# CSC_Connections_Temp.net
KiCad netlist of a schematic drawn in Altium Designer
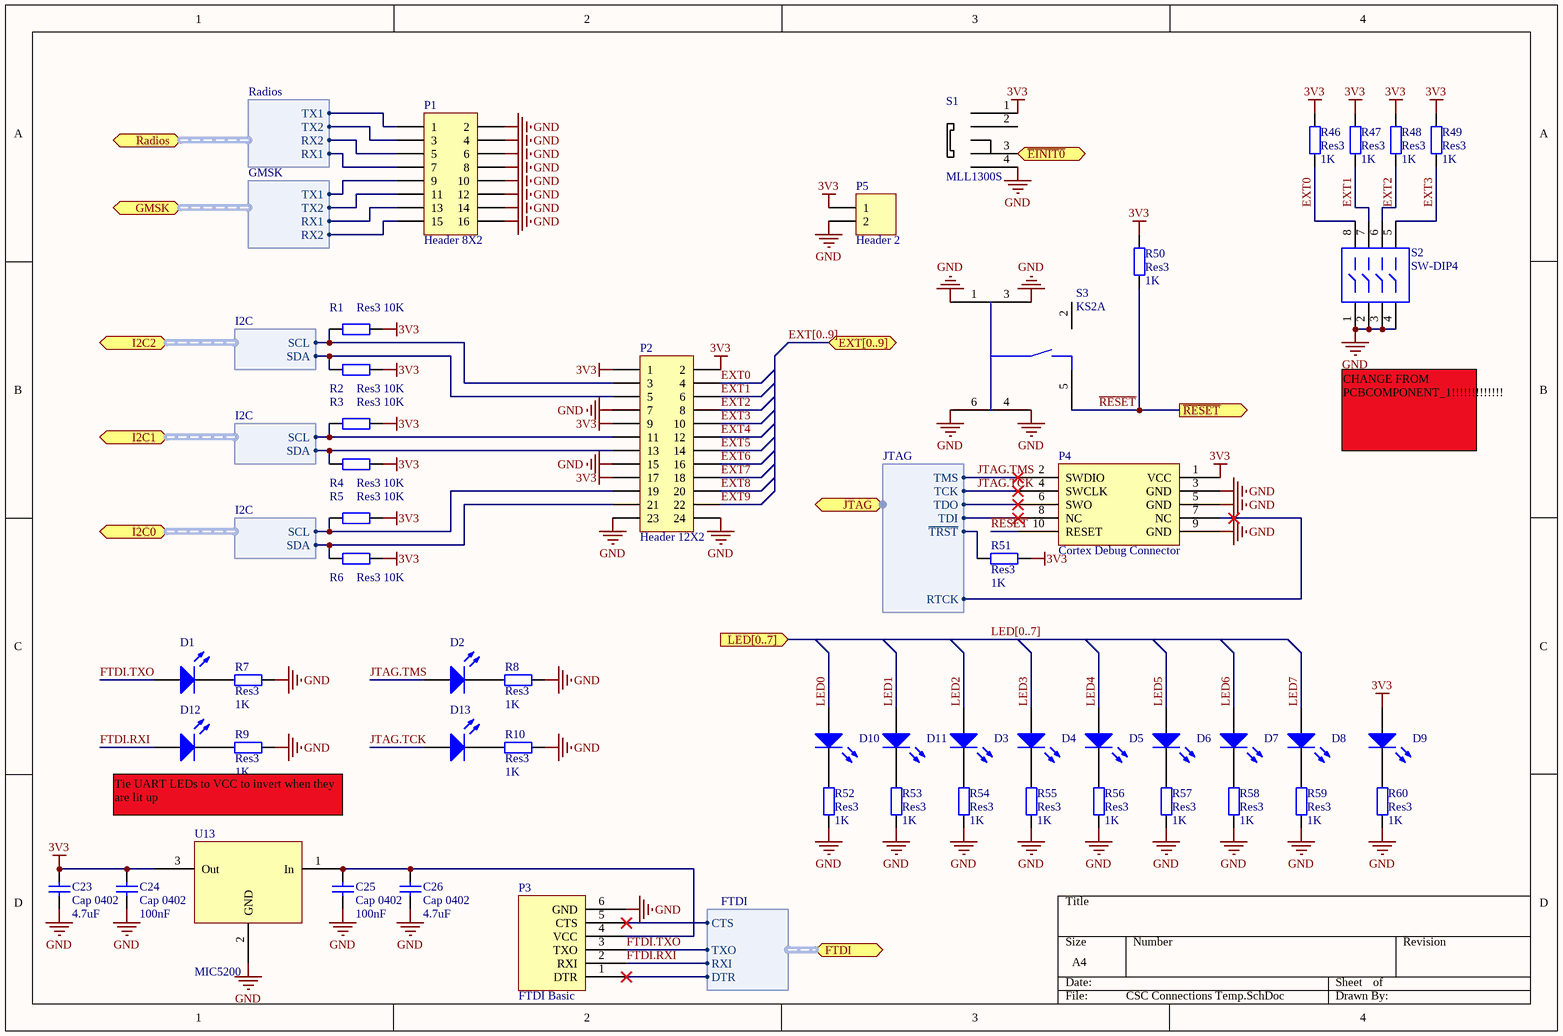
[diagram p0: CSC Connections Temp.SchDoc]

(export (version "E")
  (design (tool "Eeschema 10.0.6"))
  (components
    (comp (ref "C23")
      (value "Cap 0402")
      (footprint "CAPC1005X06L")
      (description "Capacitor")
      (fields (field (name "ALTIUM_VALUE") "4.7uF") (field (name "PUBLISHER") "Altium Limited"))
      (libsource (lib "CSC") (part "Cap 0402"))
    )
    (comp (ref "C24")
      (value "Cap 0402")
      (footprint "CAPC1005X06L")
      (description "Capacitor")
      (fields (field (name "ALTIUM_VALUE") "100nF") (field (name "PUBLISHER") "Altium Limited"))
      (libsource (lib "CSC") (part "Cap 0402"))
    )
    (comp (ref "C25")
      (value "Cap 0402")
      (footprint "CAPC1005X06L")
      (description "Capacitor")
      (fields (field (name "ALTIUM_VALUE") "100nF") (field (name "PUBLISHER") "Altium Limited"))
      (libsource (lib "CSC") (part "Cap 0402"))
    )
    (comp (ref "C26")
      (value "Cap 0402")
      (footprint "CAPC1005X06L")
      (description "Capacitor")
      (fields (field (name "ALTIUM_VALUE") "4.7uF") (field (name "PUBLISHER") "Altium Limited"))
      (libsource (lib "CSC") (part "Cap 0402"))
    )
    (comp (ref "D1")
      (value "LED - ASMT-Rx45")
      (footprint "ASMT-Rx45")
      (description "Typical INFRARED GaAs LED 0603")
      (fields (field (name "PUBLISHER") "Altium Limited"))
      (libsource (lib "CSC") (part "LED"))
    )
    (comp (ref "D2")
      (value "LED - ASMT-Rx45")
      (footprint "ASMT-Rx45")
      (description "Typical INFRARED GaAs LED 0603")
      (fields (field (name "PUBLISHER") "Altium Limited"))
      (libsource (lib "CSC") (part "LED"))
    )
    (comp (ref "D3")
      (value "LED - ASMT-Rx45")
      (footprint "ASMT-Rx45")
      (description "Typical INFRARED GaAs LED 0603")
      (fields (field (name "PUBLISHER") "Altium Limited"))
      (libsource (lib "CSC") (part "LED"))
    )
    (comp (ref "D4")
      (value "LED - ASMT-Rx45")
      (footprint "ASMT-Rx45")
      (description "Typical INFRARED GaAs LED 0603")
      (fields (field (name "PUBLISHER") "Altium Limited"))
      (libsource (lib "CSC") (part "LED"))
    )
    (comp (ref "D5")
      (value "LED - ASMT-Rx45")
      (footprint "ASMT-Rx45")
      (description "Typical INFRARED GaAs LED 0603")
      (fields (field (name "PUBLISHER") "Altium Limited"))
      (libsource (lib "CSC") (part "LED"))
    )
    (comp (ref "D6")
      (value "LED - ASMT-Rx45")
      (footprint "ASMT-Rx45")
      (description "Typical INFRARED GaAs LED 0603")
      (fields (field (name "PUBLISHER") "Altium Limited"))
      (libsource (lib "CSC") (part "LED"))
    )
    (comp (ref "D7")
      (value "LED - ASMT-Rx45")
      (footprint "ASMT-Rx45")
      (description "Typical INFRARED GaAs LED 0603")
      (fields (field (name "PUBLISHER") "Altium Limited"))
      (libsource (lib "CSC") (part "LED"))
    )
    (comp (ref "D8")
      (value "LED - ASMT-Rx45")
      (footprint "ASMT-Rx45")
      (description "Typical INFRARED GaAs LED 0603")
      (fields (field (name "PUBLISHER") "Altium Limited"))
      (libsource (lib "CSC") (part "LED"))
    )
    (comp (ref "D9")
      (value "LED - ASMT-Rx45")
      (footprint "ASMT-Rx45")
      (description "Typical INFRARED GaAs LED 0603")
      (fields (field (name "PUBLISHER") "Altium Limited"))
      (libsource (lib "CSC") (part "LED"))
    )
    (comp (ref "D10")
      (value "LED - ASMT-Rx45")
      (footprint "ASMT-Rx45")
      (description "Typical INFRARED GaAs LED 0603")
      (fields (field (name "PUBLISHER") "Altium Limited"))
      (libsource (lib "CSC") (part "LED"))
    )
    (comp (ref "D11")
      (value "LED - ASMT-Rx45")
      (footprint "ASMT-Rx45")
      (description "Typical INFRARED GaAs LED 0603")
      (fields (field (name "PUBLISHER") "Altium Limited"))
      (libsource (lib "CSC") (part "LED"))
    )
    (comp (ref "D12")
      (value "LED - ASMT-Rx45")
      (footprint "ASMT-Rx45")
      (description "Typical INFRARED GaAs LED 0603")
      (fields (field (name "PUBLISHER") "Altium Limited"))
      (libsource (lib "CSC") (part "LED"))
    )
    (comp (ref "D13")
      (value "LED - ASMT-Rx45")
      (footprint "ASMT-Rx45")
      (description "Typical INFRARED GaAs LED 0603")
      (fields (field (name "PUBLISHER") "Altium Limited"))
      (libsource (lib "CSC") (part "LED"))
    )
    (comp (ref "P1")
      (value "Header 8X2")
      (footprint "HDR2X8")
      (description "Header, 8-Pin, Dual row")
      (fields (field (name "PUBLISHER") "Altium Limited"))
      (libsource (lib "Miscellaneous Connectors") (part "Header 8X2"))
    )
    (comp (ref "P2")
      (value "Header 12X2")
      (footprint "HDR2X12")
      (description "Header, 12-Pin, Dual row")
      (fields (field (name "PUBLISHER") "Altium Limited"))
      (libsource (lib "Miscellaneous Connectors") (part "Header 12X2"))
    )
    (comp (ref "P3")
      (value "FTDI Basic")
      (footprint "FTDI BASIC")
      (libsource (lib "CSC") (part "FTDI Basic"))
    )
    (comp (ref "P4")
      (value "Cortex Debug Connector")
      (footprint "FTSH-105-01-L-DV-TR")
      (description "Mates with FFSD-05-D-12.00-01-N")
      (libsource (lib "CSC") (part "Cortex Debug Connector"))
    )
    (comp (ref "P5")
      (value "Header 2")
      (footprint "HDR1X2")
      (description "Header, 2-Pin")
      (fields (field (name "PUBLISHER") "Altium Limited"))
      (libsource (lib "Miscellaneous Connectors") (part "Header 2"))
    )
    (comp (ref "R1")
      (value "Res3")
      (footprint "RESC1005X06L")
      (description "Resistor")
      (fields (field (name "ALTIUM_VALUE") "10K") (field (name "PUBLISHER") "Altium Limited"))
      (libsource (lib "") (part "Res3_1"))
    )
    (comp (ref "R2")
      (value "Res3")
      (footprint "RESC1005X06L")
      (description "Resistor")
      (fields (field (name "ALTIUM_VALUE") "10K") (field (name "PUBLISHER") "Altium Limited"))
      (libsource (lib "") (part "Res3_1"))
    )
    (comp (ref "R3")
      (value "Res3")
      (footprint "RESC1005X06L")
      (description "Resistor")
      (fields (field (name "ALTIUM_VALUE") "10K") (field (name "PUBLISHER") "Altium Limited"))
      (libsource (lib "") (part "Res3_1"))
    )
    (comp (ref "R4")
      (value "Res3")
      (footprint "RESC1005X06L")
      (description "Resistor")
      (fields (field (name "ALTIUM_VALUE") "10K") (field (name "PUBLISHER") "Altium Limited"))
      (libsource (lib "") (part "Res3_1"))
    )
    (comp (ref "R5")
      (value "Res3")
      (footprint "RESC1005X06L")
      (description "Resistor")
      (fields (field (name "ALTIUM_VALUE") "10K") (field (name "PUBLISHER") "Altium Limited"))
      (libsource (lib "") (part "Res3_1"))
    )
    (comp (ref "R6")
      (value "Res3")
      (footprint "RESC1005X06L")
      (description "Resistor")
      (fields (field (name "ALTIUM_VALUE") "10K") (field (name "PUBLISHER") "Altium Limited"))
      (libsource (lib "") (part "Res3_1"))
    )
    (comp (ref "R7")
      (value "Res3")
      (footprint "RESC1005X06L")
      (description "Resistor")
      (fields (field (name "ALTIUM_VALUE") "1K") (field (name "PUBLISHER") "Altium Limited"))
      (libsource (lib "") (part "Res3_1"))
    )
    (comp (ref "R8")
      (value "Res3")
      (footprint "RESC1005X06L")
      (description "Resistor")
      (fields (field (name "ALTIUM_VALUE") "1K") (field (name "PUBLISHER") "Altium Limited"))
      (libsource (lib "") (part "Res3_1"))
    )
    (comp (ref "R9")
      (value "Res3")
      (footprint "RESC1005X06L")
      (description "Resistor")
      (fields (field (name "ALTIUM_VALUE") "1K") (field (name "PUBLISHER") "Altium Limited"))
      (libsource (lib "") (part "Res3_1"))
    )
    (comp (ref "R10")
      (value "Res3")
      (footprint "RESC1005X06L")
      (description "Resistor")
      (fields (field (name "ALTIUM_VALUE") "1K") (field (name "PUBLISHER") "Altium Limited"))
      (libsource (lib "") (part "Res3_1"))
    )
    (comp (ref "R46")
      (value "Res3")
      (footprint "RESC1005X06L")
      (description "Resistor")
      (fields (field (name "ALTIUM_VALUE") "1K") (field (name "PUBLISHER") "Altium Limited"))
      (libsource (lib "CSC") (part "Res3"))
    )
    (comp (ref "R47")
      (value "Res3")
      (footprint "RESC1005X06L")
      (description "Resistor")
      (fields (field (name "ALTIUM_VALUE") "1K") (field (name "PUBLISHER") "Altium Limited"))
      (libsource (lib "CSC") (part "Res3"))
    )
    (comp (ref "R48")
      (value "Res3")
      (footprint "RESC1005X06L")
      (description "Resistor")
      (fields (field (name "ALTIUM_VALUE") "1K") (field (name "PUBLISHER") "Altium Limited"))
      (libsource (lib "CSC") (part "Res3"))
    )
    (comp (ref "R49")
      (value "Res3")
      (footprint "RESC1005X06L")
      (description "Resistor")
      (fields (field (name "ALTIUM_VALUE") "1K") (field (name "PUBLISHER") "Altium Limited"))
      (libsource (lib "CSC") (part "Res3"))
    )
    (comp (ref "R50")
      (value "Res3")
      (footprint "RESC1005X06L")
      (description "Resistor")
      (fields (field (name "ALTIUM_VALUE") "1K") (field (name "PUBLISHER") "Altium Limited"))
      (libsource (lib "CSC") (part "Res3"))
    )
    (comp (ref "R51")
      (value "Res3")
      (footprint "RESC1005X06L")
      (description "Resistor")
      (fields (field (name "ALTIUM_VALUE") "1K") (field (name "PUBLISHER") "Altium Limited"))
      (libsource (lib "") (part "Res3_1"))
    )
    (comp (ref "R52")
      (value "Res3")
      (footprint "RESC1005X06L")
      (description "Resistor")
      (fields (field (name "ALTIUM_VALUE") "1K") (field (name "PUBLISHER") "Altium Limited"))
      (libsource (lib "CSC") (part "Res3"))
    )
    (comp (ref "R53")
      (value "Res3")
      (footprint "RESC1005X06L")
      (description "Resistor")
      (fields (field (name "ALTIUM_VALUE") "1K") (field (name "PUBLISHER") "Altium Limited"))
      (libsource (lib "CSC") (part "Res3"))
    )
    (comp (ref "R54")
      (value "Res3")
      (footprint "RESC1005X06L")
      (description "Resistor")
      (fields (field (name "ALTIUM_VALUE") "1K") (field (name "PUBLISHER") "Altium Limited"))
      (libsource (lib "CSC") (part "Res3"))
    )
    (comp (ref "R55")
      (value "Res3")
      (footprint "RESC1005X06L")
      (description "Resistor")
      (fields (field (name "ALTIUM_VALUE") "1K") (field (name "PUBLISHER") "Altium Limited"))
      (libsource (lib "CSC") (part "Res3"))
    )
    (comp (ref "R56")
      (value "Res3")
      (footprint "RESC1005X06L")
      (description "Resistor")
      (fields (field (name "ALTIUM_VALUE") "1K") (field (name "PUBLISHER") "Altium Limited"))
      (libsource (lib "CSC") (part "Res3"))
    )
    (comp (ref "R57")
      (value "Res3")
      (footprint "RESC1005X06L")
      (description "Resistor")
      (fields (field (name "ALTIUM_VALUE") "1K") (field (name "PUBLISHER") "Altium Limited"))
      (libsource (lib "CSC") (part "Res3"))
    )
    (comp (ref "R58")
      (value "Res3")
      (footprint "RESC1005X06L")
      (description "Resistor")
      (fields (field (name "ALTIUM_VALUE") "1K") (field (name "PUBLISHER") "Altium Limited"))
      (libsource (lib "CSC") (part "Res3"))
    )
    (comp (ref "R59")
      (value "Res3")
      (footprint "RESC1005X06L")
      (description "Resistor")
      (fields (field (name "ALTIUM_VALUE") "1K") (field (name "PUBLISHER") "Altium Limited"))
      (libsource (lib "CSC") (part "Res3"))
    )
    (comp (ref "R60")
      (value "Res3")
      (footprint "RESC1005X06L")
      (description "Resistor")
      (fields (field (name "ALTIUM_VALUE") "1K") (field (name "PUBLISHER") "Altium Limited"))
      (libsource (lib "CSC") (part "Res3"))
    )
    (comp (ref "S1")
      (value "MLL1300S")
      (footprint "MILL1300S")
      (description "Slide switch SP3T switch")
      (libsource (lib "CSC") (part "MLL1300S"))
    )
    (comp (ref "S2")
      (value "SW-DIP4")
      (footprint "PCBComponent_1")
      (description "DIP Switch - 1571983-5")
      (fields (field (name "PUBLISHER") "Altium Limited"))
      (libsource (lib "CSC") (part "SW-DIP4"))
    )
    (comp (ref "S3")
      (value "KS2A")
      (footprint "K5A2")
      (description "Tact Switch")
      (libsource (lib "CSC") (part "KS2A"))
    )
    (comp (ref "U13")
      (value "MIC5200")
      (footprint "SOT230P710X170-4L")
      (libsource (lib "CSC") (part "MIC5200"))
    )
  )
  (nets
    (net (code "6") (name "/CTS") (class "Default")
      (node (ref "P3") (pin "5") (pinfunction "CTS_5") (pintype "passive+no_connect"))
    )
    (net (code "7") (name "/DTR") (class "Default")
      (node (ref "P3") (pin "1") (pinfunction "DTR_1") (pintype "passive+no_connect"))
    )
    (net (code "8") (name "/EXT0") (class "Default")
      (node (ref "P2") (pin "4") (pinfunction "4_4") (pintype "passive"))
      (node (ref "R46") (pin "2") (pinfunction "2_2") (pintype "passive"))
      (node (ref "S2") (pin "8") (pinfunction "8_8") (pintype "passive"))
    )
    (net (code "9") (name "/EXT1") (class "Default")
      (node (ref "P2") (pin "6") (pinfunction "6_6") (pintype "passive"))
      (node (ref "R47") (pin "2") (pinfunction "2_2") (pintype "passive"))
      (node (ref "S2") (pin "7") (pinfunction "7_7") (pintype "passive"))
    )
    (net (code "10") (name "/EXT2") (class "Default")
      (node (ref "P2") (pin "8") (pinfunction "8_8") (pintype "passive"))
      (node (ref "R48") (pin "2") (pinfunction "2_2") (pintype "passive"))
      (node (ref "S2") (pin "6") (pinfunction "6_6") (pintype "passive"))
    )
    (net (code "11") (name "/EXT3") (class "Default")
      (node (ref "P2") (pin "10") (pinfunction "10_10") (pintype "passive"))
      (node (ref "R49") (pin "2") (pinfunction "2_2") (pintype "passive"))
      (node (ref "S2") (pin "5") (pinfunction "5_5") (pintype "passive"))
    )
    (net (code "12") (name "/EXT4") (class "Default")
      (node (ref "P2") (pin "12") (pinfunction "12_12") (pintype "passive"))
    )
    (net (code "13") (name "/EXT5") (class "Default")
      (node (ref "P2") (pin "14") (pinfunction "14_14") (pintype "passive"))
    )
    (net (code "14") (name "/EXT6") (class "Default")
      (node (ref "P2") (pin "16") (pinfunction "16_16") (pintype "passive"))
    )
    (net (code "15") (name "/EXT7") (class "Default")
      (node (ref "P2") (pin "18") (pinfunction "18_18") (pintype "passive"))
    )
    (net (code "16") (name "/EXT8") (class "Default")
      (node (ref "P2") (pin "20") (pinfunction "20_20") (pintype "passive"))
    )
    (net (code "17") (name "/EXT9") (class "Default")
      (node (ref "P2") (pin "22") (pinfunction "22_22") (pintype "passive"))
    )
    (net (code "19") (name "/FTDI.RXI") (class "Default")
      (node (ref "D12") (pin "1") (pinfunction "A_1") (pintype "passive"))
      (node (ref "P3") (pin "2") (pinfunction "RXI_2") (pintype "passive"))
    )
    (net (code "20") (name "/FTDI.TXO") (class "Default")
      (node (ref "D1") (pin "1") (pinfunction "A_1") (pintype "passive"))
      (node (ref "P3") (pin "3") (pinfunction "TXO_3") (pintype "passive"))
    )
    (net (code "21") (name "/JTAG.TCK") (class "Default")
      (node (ref "D13") (pin "1") (pinfunction "A_1") (pintype "passive"))
      (node (ref "P4") (pin "4") (pinfunction "SWCLK_4") (pintype "passive"))
    )
    (net (code "22") (name "/JTAG.TMS") (class "Default")
      (node (ref "D2") (pin "1") (pinfunction "A_1") (pintype "passive"))
      (node (ref "P4") (pin "2") (pinfunction "SWDIO_2") (pintype "passive"))
    )
    (net (code "23") (name "/LED0") (class "Default")
      (node (ref "D10") (pin "1") (pinfunction "A_1") (pintype "passive"))
    )
    (net (code "24") (name "/LED1") (class "Default")
      (node (ref "D11") (pin "1") (pinfunction "A_1") (pintype "passive"))
    )
    (net (code "25") (name "/LED2") (class "Default")
      (node (ref "D3") (pin "1") (pinfunction "A_1") (pintype "passive"))
    )
    (net (code "26") (name "/LED3") (class "Default")
      (node (ref "D4") (pin "1") (pinfunction "A_1") (pintype "passive"))
    )
    (net (code "27") (name "/LED4") (class "Default")
      (node (ref "D5") (pin "1") (pinfunction "A_1") (pintype "passive"))
    )
    (net (code "28") (name "/LED5") (class "Default")
      (node (ref "D6") (pin "1") (pinfunction "A_1") (pintype "passive"))
    )
    (net (code "29") (name "/LED6") (class "Default")
      (node (ref "D7") (pin "1") (pinfunction "A_1") (pintype "passive"))
    )
    (net (code "30") (name "/LED7") (class "Default")
      (node (ref "D8") (pin "1") (pinfunction "A_1") (pintype "passive"))
    )
    (net (code "32") (name "/RTCK") (class "Default")
      (node (ref "P4") (pin "7") (pinfunction "NC_7") (pintype "passive"))
    )
    (net (code "33") (name "/TDI") (class "Default")
      (node (ref "P4") (pin "8") (pinfunction "NC_8") (pintype "passive+no_connect"))
    )
    (net (code "34") (name "/TDO") (class "Default")
      (node (ref "P4") (pin "6") (pinfunction "SWO_6") (pintype "passive+no_connect"))
    )
    (net (code "40") (name "/~{EINIT0}") (class "Default")
      (node (ref "S1") (pin "3") (pinfunction "3_3") (pintype "passive"))
    )
    (net (code "41") (name "/~{RESET}") (class "Default")
      (node (ref "P4") (pin "10") (pinfunction "RESET_10") (pintype "passive"))
      (node (ref "R50") (pin "2") (pinfunction "2_2") (pintype "passive"))
      (node (ref "S3") (pin "5") (pinfunction "5_5") (pintype "passive"))
    )
    (net (code "42") (name "/~{TRST}") (class "Default")
      (node (ref "R51") (pin "1") (pinfunction "1_1") (pintype "passive"))
    )
    (net (code "43") (name "3V3") (class "Default")
      (node (ref "C23") (pin "2") (pinfunction "2_2") (pintype "passive"))
      (node (ref "C24") (pin "2") (pinfunction "2_2") (pintype "passive"))
      (node (ref "D9") (pin "1") (pinfunction "A_1") (pintype "passive"))
      (node (ref "P2") (pin "1") (pinfunction "1_1") (pintype "passive"))
      (node (ref "P2") (pin "17") (pinfunction "17_17") (pintype "passive"))
      (node (ref "P2") (pin "2") (pinfunction "2_2") (pintype "passive"))
      (node (ref "P2") (pin "9") (pinfunction "9_9") (pintype "passive"))
      (node (ref "P4") (pin "1") (pinfunction "VCC_1") (pintype "passive"))
      (node (ref "P5") (pin "1") (pinfunction "1_1") (pintype "passive"))
      (node (ref "R1") (pin "2") (pinfunction "2_2") (pintype "passive"))
      (node (ref "R2") (pin "2") (pinfunction "2_2") (pintype "passive"))
      (node (ref "R3") (pin "2") (pinfunction "2_2") (pintype "passive"))
      (node (ref "R4") (pin "2") (pinfunction "2_2") (pintype "passive"))
      (node (ref "R46") (pin "1") (pinfunction "1_1") (pintype "passive"))
      (node (ref "R47") (pin "1") (pinfunction "1_1") (pintype "passive"))
      (node (ref "R48") (pin "1") (pinfunction "1_1") (pintype "passive"))
      (node (ref "R49") (pin "1") (pinfunction "1_1") (pintype "passive"))
      (node (ref "R5") (pin "2") (pinfunction "2_2") (pintype "passive"))
      (node (ref "R50") (pin "1") (pinfunction "1_1") (pintype "passive"))
      (node (ref "R51") (pin "2") (pinfunction "2_2") (pintype "passive"))
      (node (ref "R6") (pin "2") (pinfunction "2_2") (pintype "passive"))
      (node (ref "S1") (pin "1") (pinfunction "1_1") (pintype "passive"))
      (node (ref "U13") (pin "3") (pinfunction "Out_3") (pintype "power_in"))
    )
    (net (code "44") (name "GND") (class "Default")
      (node (ref "C23") (pin "1") (pinfunction "1_1") (pintype "passive"))
      (node (ref "C24") (pin "1") (pinfunction "1_1") (pintype "passive"))
      (node (ref "C25") (pin "1") (pinfunction "1_1") (pintype "passive"))
      (node (ref "C26") (pin "1") (pinfunction "1_1") (pintype "passive"))
      (node (ref "P1") (pin "10") (pinfunction "10_10") (pintype "passive"))
      (node (ref "P1") (pin "12") (pinfunction "12_12") (pintype "passive"))
      (node (ref "P1") (pin "14") (pinfunction "14_14") (pintype "passive"))
      (node (ref "P1") (pin "16") (pinfunction "16_16") (pintype "passive"))
      (node (ref "P1") (pin "2") (pinfunction "2_2") (pintype "passive"))
      (node (ref "P1") (pin "4") (pinfunction "4_4") (pintype "passive"))
      (node (ref "P1") (pin "6") (pinfunction "6_6") (pintype "passive"))
      (node (ref "P1") (pin "8") (pinfunction "8_8") (pintype "passive"))
      (node (ref "P2") (pin "15") (pinfunction "15_15") (pintype "passive"))
      (node (ref "P2") (pin "23") (pinfunction "23_23") (pintype "passive"))
      (node (ref "P2") (pin "24") (pinfunction "24_24") (pintype "passive"))
      (node (ref "P2") (pin "7") (pinfunction "7_7") (pintype "passive"))
      (node (ref "P3") (pin "6") (pinfunction "GND_6") (pintype "passive"))
      (node (ref "P4") (pin "3") (pinfunction "GND_3") (pintype "passive"))
      (node (ref "P4") (pin "5") (pinfunction "GND_5") (pintype "passive"))
      (node (ref "P4") (pin "9") (pinfunction "GND_9") (pintype "passive"))
      (node (ref "P5") (pin "2") (pinfunction "2_2") (pintype "passive"))
      (node (ref "R10") (pin "2") (pinfunction "2_2") (pintype "passive"))
      (node (ref "R52") (pin "2") (pinfunction "2_2") (pintype "passive"))
      (node (ref "R53") (pin "2") (pinfunction "2_2") (pintype "passive"))
      (node (ref "R54") (pin "2") (pinfunction "2_2") (pintype "passive"))
      (node (ref "R55") (pin "2") (pinfunction "2_2") (pintype "passive"))
      (node (ref "R56") (pin "2") (pinfunction "2_2") (pintype "passive"))
      (node (ref "R57") (pin "2") (pinfunction "2_2") (pintype "passive"))
      (node (ref "R58") (pin "2") (pinfunction "2_2") (pintype "passive"))
      (node (ref "R59") (pin "2") (pinfunction "2_2") (pintype "passive"))
      (node (ref "R60") (pin "2") (pinfunction "2_2") (pintype "passive"))
      (node (ref "R7") (pin "2") (pinfunction "2_2") (pintype "passive"))
      (node (ref "R8") (pin "2") (pinfunction "2_2") (pintype "passive"))
      (node (ref "R9") (pin "2") (pinfunction "2_2") (pintype "passive"))
      (node (ref "S1") (pin "4") (pinfunction "4_4") (pintype "passive"))
      (node (ref "S2") (pin "1") (pinfunction "1_1") (pintype "passive"))
      (node (ref "S2") (pin "2") (pinfunction "2_2") (pintype "passive"))
      (node (ref "S2") (pin "3") (pinfunction "3_3") (pintype "passive"))
      (node (ref "S2") (pin "4") (pinfunction "4_4") (pintype "passive"))
      (node (ref "S3") (pin "1") (pinfunction "1_1") (pintype "power_in"))
      (node (ref "S3") (pin "3") (pinfunction "3_3") (pintype "power_in"))
      (node (ref "S3") (pin "4") (pinfunction "4_4") (pintype "power_in"))
      (node (ref "S3") (pin "6") (pinfunction "6_6") (pintype "power_in"))
      (node (ref "U13") (pin "2") (pinfunction "GND_2") (pintype "power_in"))
    )
    (net (code "45") (name "Net-(D1-K)") (class "Default")
      (node (ref "D1") (pin "2") (pinfunction "K_2") (pintype "passive"))
      (node (ref "R7") (pin "1") (pinfunction "1_1") (pintype "passive"))
    )
    (net (code "46") (name "Net-(D2-K)") (class "Default")
      (node (ref "D2") (pin "2") (pinfunction "K_2") (pintype "passive"))
      (node (ref "R8") (pin "1") (pinfunction "1_1") (pintype "passive"))
    )
    (net (code "47") (name "Net-(D3-K)") (class "Default")
      (node (ref "D3") (pin "2") (pinfunction "K_2") (pintype "passive"))
      (node (ref "R54") (pin "1") (pinfunction "1_1") (pintype "passive"))
    )
    (net (code "48") (name "Net-(D4-K)") (class "Default")
      (node (ref "D4") (pin "2") (pinfunction "K_2") (pintype "passive"))
      (node (ref "R55") (pin "1") (pinfunction "1_1") (pintype "passive"))
    )
    (net (code "49") (name "Net-(D5-K)") (class "Default")
      (node (ref "D5") (pin "2") (pinfunction "K_2") (pintype "passive"))
      (node (ref "R56") (pin "1") (pinfunction "1_1") (pintype "passive"))
    )
    (net (code "50") (name "Net-(D6-K)") (class "Default")
      (node (ref "D6") (pin "2") (pinfunction "K_2") (pintype "passive"))
      (node (ref "R57") (pin "1") (pinfunction "1_1") (pintype "passive"))
    )
    (net (code "51") (name "Net-(D7-K)") (class "Default")
      (node (ref "D7") (pin "2") (pinfunction "K_2") (pintype "passive"))
      (node (ref "R58") (pin "1") (pinfunction "1_1") (pintype "passive"))
    )
    (net (code "52") (name "Net-(D8-K)") (class "Default")
      (node (ref "D8") (pin "2") (pinfunction "K_2") (pintype "passive"))
      (node (ref "R59") (pin "1") (pinfunction "1_1") (pintype "passive"))
    )
    (net (code "53") (name "Net-(D9-K)") (class "Default")
      (node (ref "D9") (pin "2") (pinfunction "K_2") (pintype "passive"))
      (node (ref "R60") (pin "1") (pinfunction "1_1") (pintype "passive"))
    )
    (net (code "54") (name "Net-(D10-K)") (class "Default")
      (node (ref "D10") (pin "2") (pinfunction "K_2") (pintype "passive"))
      (node (ref "R52") (pin "1") (pinfunction "1_1") (pintype "passive"))
    )
    (net (code "55") (name "Net-(D11-K)") (class "Default")
      (node (ref "D11") (pin "2") (pinfunction "K_2") (pintype "passive"))
      (node (ref "R53") (pin "1") (pinfunction "1_1") (pintype "passive"))
    )
    (net (code "56") (name "Net-(D12-K)") (class "Default")
      (node (ref "D12") (pin "2") (pinfunction "K_2") (pintype "passive"))
      (node (ref "R9") (pin "1") (pinfunction "1_1") (pintype "passive"))
    )
    (net (code "57") (name "Net-(D13-K)") (class "Default")
      (node (ref "D13") (pin "2") (pinfunction "K_2") (pintype "passive"))
      (node (ref "R10") (pin "1") (pinfunction "1_1") (pintype "passive"))
    )
    (net (code "58") (name "Net-(P2-Pad3)") (class "Default")
      (node (ref "P2") (pin "3") (pinfunction "3_3") (pintype "passive"))
      (node (ref "R1") (pin "1") (pinfunction "1_1") (pintype "passive"))
    )
    (net (code "59") (name "Net-(P2-Pad5)") (class "Default")
      (node (ref "P2") (pin "5") (pinfunction "5_5") (pintype "passive"))
      (node (ref "R2") (pin "1") (pinfunction "1_1") (pintype "passive"))
    )
    (net (code "60") (name "Net-(P2-Pad11)") (class "Default")
      (node (ref "P2") (pin "11") (pinfunction "11_11") (pintype "passive"))
      (node (ref "R3") (pin "1") (pinfunction "1_1") (pintype "passive"))
    )
    (net (code "61") (name "Net-(P2-Pad13)") (class "Default")
      (node (ref "P2") (pin "13") (pinfunction "13_13") (pintype "passive"))
      (node (ref "R4") (pin "1") (pinfunction "1_1") (pintype "passive"))
    )
    (net (code "62") (name "Net-(P2-Pad19)") (class "Default")
      (node (ref "P2") (pin "19") (pinfunction "19_19") (pintype "passive"))
      (node (ref "R5") (pin "1") (pinfunction "1_1") (pintype "passive"))
    )
    (net (code "63") (name "Net-(P2-Pad21)") (class "Default")
      (node (ref "P2") (pin "21") (pinfunction "21_21") (pintype "passive"))
      (node (ref "R6") (pin "1") (pinfunction "1_1") (pintype "passive"))
    )
    (net (code "64") (name "Net-(P3-VCC)") (class "Default")
      (node (ref "C25") (pin "2") (pinfunction "2_2") (pintype "passive"))
      (node (ref "C26") (pin "2") (pinfunction "2_2") (pintype "passive"))
      (node (ref "P3") (pin "4") (pinfunction "VCC_4") (pintype "passive"))
      (node (ref "U13") (pin "1") (pinfunction "In_1") (pintype "power_in"))
    )
    (net (code "65") (name "unconnected-(P1-Pad1)") (class "Default")
      (node (ref "P1") (pin "1") (pinfunction "1_1") (pintype "passive"))
    )
    (net (code "66") (name "unconnected-(P1-Pad3)") (class "Default")
      (node (ref "P1") (pin "3") (pinfunction "3_3") (pintype "passive"))
    )
    (net (code "67") (name "unconnected-(P1-Pad5)") (class "Default")
      (node (ref "P1") (pin "5") (pinfunction "5_5") (pintype "passive"))
    )
    (net (code "68") (name "unconnected-(P1-Pad7)") (class "Default")
      (node (ref "P1") (pin "7") (pinfunction "7_7") (pintype "passive"))
    )
    (net (code "69") (name "unconnected-(P1-Pad9)") (class "Default")
      (node (ref "P1") (pin "9") (pinfunction "9_9") (pintype "passive"))
    )
    (net (code "70") (name "unconnected-(P1-Pad11)") (class "Default")
      (node (ref "P1") (pin "11") (pinfunction "11_11") (pintype "passive"))
    )
    (net (code "71") (name "unconnected-(P1-Pad13)") (class "Default")
      (node (ref "P1") (pin "13") (pinfunction "13_13") (pintype "passive"))
    )
    (net (code "72") (name "unconnected-(P1-Pad15)") (class "Default")
      (node (ref "P1") (pin "15") (pinfunction "15_15") (pintype "passive"))
    )
    (net (code "73") (name "unconnected-(S1-Pad2)") (class "Default")
      (node (ref "S1") (pin "2") (pinfunction "2_2") (pintype "passive"))
    )
    (net (code "74") (name "unconnected-(S3-Pad2)") (class "Default")
      (node (ref "S3") (pin "2") (pinfunction "2_2") (pintype "power_in"))
    )
  )
)
